# ESP32.net
KiCad netlist of a schematic drawn in Altium Designer
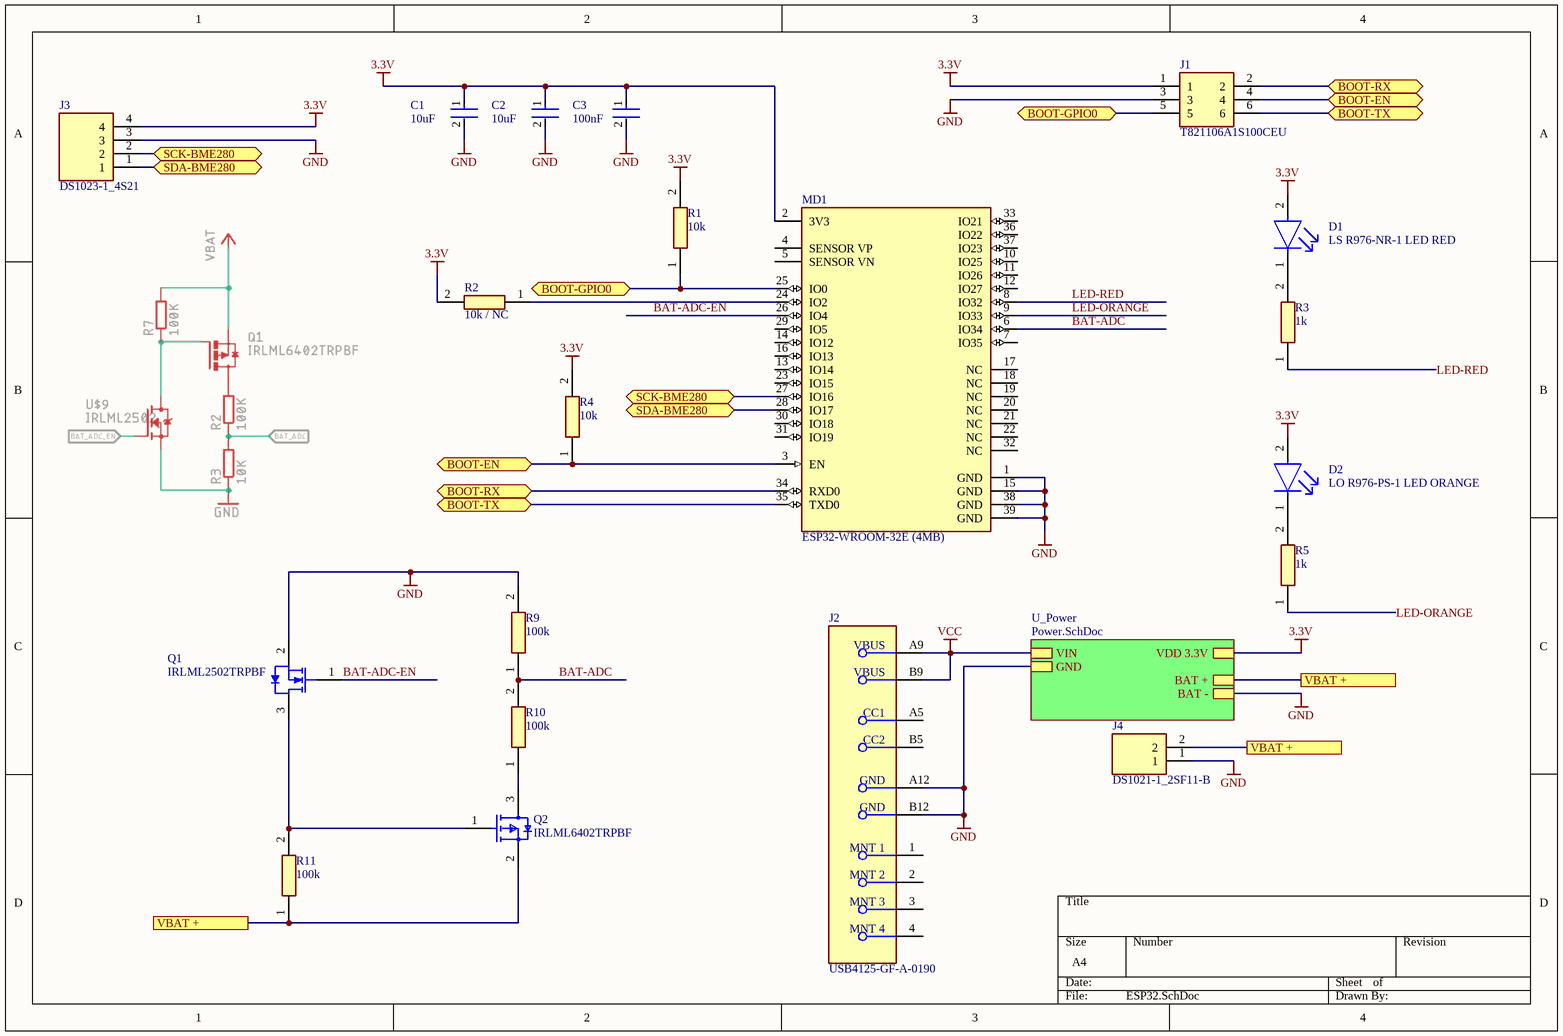
[diagram p0: ESP32.SchDoc]

(export (version "E")
  (design (tool "Eeschema 10.0.6"))
  (components
    (comp (ref "C1")
      (value "10uF")
      (footprint "FP-0805-L_2_01_0_2-W_1_25-IPC_B")
      (description "Automotive Ceramic Capacitor, 0805, 22nF, 5%, X7R, 15%, 100V")
      (fields (field (name "TOLERANCE") "5%"))
      (libsource (lib "Altium Content Vault") (part "b4654b650e69147ec39a6b967a45e02"))
    )
    (comp (ref "C2")
      (value "10uF")
      (footprint "FP-0805-L_2_01_0_2-W_1_25-IPC_B")
      (description "Automotive Ceramic Capacitor, 0805, 22nF, 5%, X7R, 15%, 100V")
      (fields (field (name "TOLERANCE") "5%"))
      (libsource (lib "Altium Content Vault") (part "b4654b650e69147ec39a6b967a45e02"))
    )
    (comp (ref "C3")
      (value "100nF")
      (footprint "FP-0805-L_2_01_0_2-W_1_25-IPC_B")
      (description "Automotive Ceramic Capacitor, 0805, 22nF, 5%, X7R, 15%, 100V")
      (fields (field (name "TOLERANCE") "5%"))
      (libsource (lib "Altium Content Vault") (part "b4654b650e69147ec39a6b967a45e02"))
    )
    (comp (ref "D1")
      (value "LS R976-NR-1 LED RED")
      (footprint "FP-LS_R976-MFG")
      (description "LED RED DIFFUSED 0805 SMD")
      (libsource (lib "Altium Content Vault") (part "8706943c75ba83719d021d2fdc84c58"))
    )
    (comp (ref "D2")
      (value "LO R976-PS-1 LED ORANGE")
      (footprint "FP-LO_R976-MFG")
      (description "LED ORANGE DIFFUSED 0805 SMD")
      (libsource (lib "Altium Content Vault") (part "8706943c75ba83719d021d2fdc84c58"))
    )
    (comp (ref "J1")
      (value "T821106A1S100CEU")
      (footprint "SamacSys:SHDR6W64P254X254_2X3_1524X895X915P")
      (description "Connector")
      (libsource (lib "*") (part "T821106A1S100CEU"))
    )
    (comp (ref "J2")
      (value "USB4125-GF-A-0190")
      (footprint "FP-USB4125-GF-A-0190-MFG")
      (description "CONN RCPT TYPE C 6P SMD RA")
      (libsource (lib "Altium Content Vault") (part "a055484d46e58b234844902c9fd883a"))
    )
    (comp (ref "J3")
      (value "DS1023-1_4S21")
      (footprint "SamacSys:RHDR4W60P0X254_1X4_1016X250X840P")
      (description "Connector")
      (fields (field (name "MANUFACTURER_PART_NUMBER") "DS1023-1*4S21"))
      (libsource (lib "*") (part "DS1023-1_4S21"))
    )
    (comp (ref "J4")
      (value "DS1021-1_2SF11-B")
      (footprint "SamacSys:HDRV2W64P0X254_1X2_508X254X588P")
      (description "Connector")
      (fields (field (name "MANUFACTURER_PART_NUMBER") "DS1021-1*2SF11-B"))
      (libsource (lib "SamacSys") (part "DS1021-1_2SF11-B"))
    )
    (comp (ref "MD1")
      (value "ESP32-WROOM-32E (4MB)")
      (footprint "FP-ESP32-WROOM-32E_4MB-MFG")
      (description "RX TXRX MOD WIFI TRACE ANT SMD")
      (libsource (lib "Altium Content Vault") (part "7f842c3463a9561e2f6f9fdcd687e0f"))
    )
    (comp (ref "Q1")
      (value "IRLML2502TRPBF")
      (footprint "INTR-SOT-23-3_V")
      (description "N-Channel HEXFET(R) Power MOSFET, 20 V VDS, +/- 12 V VGS, 4.2 A, 3-Pin SOT23, RoHS, Tape and Reel")
      (fields (field (name "MANUFACTURER") "International Rectifier"))
      (libsource (lib "Altium Content Vault") (part "NEMOS-GSD-3"))
    )
    (comp (ref "Q2")
      (value "IRLML6402TRPBF")
      (footprint "FP-Micro3-MFG")
      (description "MOSFET P-CH 20V 3.7A SOT-23")
      (fields
        (field (name "OCTOPART") "https://octopart.com/irlml6402trpbf-infineon-65874989")
        (field (name "MANUFACTURER") "Infineon")
      )
      (libsource (lib "Altium Content Vault") (part "566027c8dc92b5207d53ac25ab3eb60"))
    )
    (comp (ref "R1")
      (value "10k")
      (footprint "SamacSys:RESC2013X65N")
      (description "Resistor")
      (fields (field (name "MANUFACTURER_PART_NUMBER") "0805W8F1000T5E"))
      (libsource (lib "*") (part "0805W8F1000T5E"))
    )
    (comp (ref "R2")
      (value "10k / NC")
      (footprint "SamacSys:RESC2013X65N")
      (description "Resistor")
      (fields (field (name "MANUFACTURER_PART_NUMBER") "0805W8F1000T5E"))
      (libsource (lib "") (part "0805W8F1000T5E_1"))
    )
    (comp (ref "R3")
      (value "1k")
      (footprint "SamacSys:RESC2013X65N")
      (description "Resistor")
      (fields (field (name "MANUFACTURER_PART_NUMBER") "0805W8F1000T5E"))
      (libsource (lib "*") (part "0805W8F1000T5E"))
    )
    (comp (ref "R4")
      (value "10k")
      (footprint "SamacSys:RESC2013X65N")
      (description "Resistor")
      (fields (field (name "MANUFACTURER_PART_NUMBER") "0805W8F1000T5E"))
      (libsource (lib "*") (part "0805W8F1000T5E"))
    )
    (comp (ref "R5")
      (value "1k")
      (footprint "SamacSys:RESC2013X65N")
      (description "Resistor")
      (fields (field (name "MANUFACTURER_PART_NUMBER") "0805W8F1000T5E"))
      (libsource (lib "*") (part "0805W8F1000T5E"))
    )
    (comp (ref "R9")
      (value "100k")
      (footprint "SamacSys:RESC2013X65N")
      (description "Resistor")
      (fields (field (name "MANUFACTURER_PART_NUMBER") "0805W8F1000T5E"))
      (libsource (lib "*") (part "0805W8F1000T5E"))
    )
    (comp (ref "R10")
      (value "100k")
      (footprint "SamacSys:RESC2013X65N")
      (description "Resistor")
      (fields (field (name "MANUFACTURER_PART_NUMBER") "0805W8F1000T5E"))
      (libsource (lib "*") (part "0805W8F1000T5E"))
    )
    (comp (ref "R11")
      (value "100k")
      (footprint "SamacSys:RESC2013X65N")
      (description "Resistor")
      (fields (field (name "MANUFACTURER_PART_NUMBER") "0805W8F1000T5E"))
      (libsource (lib "*") (part "0805W8F1000T5E"))
    )
  )
  (nets
    (net (code "1") (name "/BAT-ADC") (class "Default")
      (node (ref "MD1") (pin "6") (pinfunction "IO34_6") (pintype "bidirectional"))
      (node (ref "R10") (pin "2") (pinfunction "2_2") (pintype "passive"))
      (node (ref "R9") (pin "1") (pinfunction "1_1") (pintype "passive"))
    )
    (net (code "2") (name "/BAT-ADC-EN") (class "Default")
      (node (ref "MD1") (pin "26") (pinfunction "IO4_26") (pintype "bidirectional"))
      (node (ref "Q1") (pin "1") (pinfunction "G_1") (pintype "passive"))
    )
    (net (code "3") (name "/BOOT-EN") (class "Default")
      (node (ref "J1") (pin "4") (pinfunction "4_4") (pintype "passive"))
      (node (ref "MD1") (pin "3") (pinfunction "EN_3") (pintype "input"))
      (node (ref "R4") (pin "1") (pinfunction "1_1") (pintype "passive"))
    )
    (net (code "4") (name "/BOOT-GPIO0") (class "Default")
      (node (ref "J1") (pin "5") (pinfunction "5_5") (pintype "passive"))
      (node (ref "MD1") (pin "25") (pinfunction "IO0_25") (pintype "bidirectional"))
      (node (ref "R1") (pin "1") (pinfunction "1_1") (pintype "passive"))
    )
    (net (code "5") (name "/BOOT-RX") (class "Default")
      (node (ref "J1") (pin "2") (pinfunction "2_2") (pintype "passive"))
      (node (ref "MD1") (pin "34") (pinfunction "RXD0_34") (pintype "bidirectional"))
    )
    (net (code "6") (name "/BOOT-TX") (class "Default")
      (node (ref "J1") (pin "6") (pinfunction "6_6") (pintype "passive"))
      (node (ref "MD1") (pin "35") (pinfunction "TXD0_35") (pintype "bidirectional"))
    )
    (net (code "7") (name "/LED-ORANGE") (class "Default")
      (node (ref "MD1") (pin "9") (pinfunction "IO33_9") (pintype "bidirectional"))
      (node (ref "R5") (pin "1") (pinfunction "1_1") (pintype "passive"))
    )
    (net (code "8") (name "/LED-RED") (class "Default")
      (node (ref "MD1") (pin "8") (pinfunction "IO32_8") (pintype "bidirectional"))
      (node (ref "R3") (pin "1") (pinfunction "1_1") (pintype "passive"))
    )
    (net (code "9") (name "/SCK-BME280") (class "Default")
      (node (ref "J3") (pin "2") (pinfunction "2_2") (pintype "passive"))
      (node (ref "MD1") (pin "27") (pinfunction "IO16_27") (pintype "bidirectional"))
    )
    (net (code "10") (name "/SDA-BME280") (class "Default")
      (node (ref "J3") (pin "1") (pinfunction "1_1") (pintype "passive"))
      (node (ref "MD1") (pin "28") (pinfunction "IO17_28") (pintype "bidirectional"))
    )
    (net (code "11") (name "/VBAT +") (class "Default")
      (node (ref "J4") (pin "2") (pinfunction "2_2") (pintype "passive"))
      (node (ref "Q2") (pin "2") (pinfunction "S_2") (pintype "passive"))
      (node (ref "R11") (pin "1") (pinfunction "1_1") (pintype "passive"))
    )
    (net (code "12") (name "3.3V") (class "Default")
      (node (ref "C1") (pin "1") (pinfunction "1_1") (pintype "passive"))
      (node (ref "C2") (pin "1") (pinfunction "1_1") (pintype "passive"))
      (node (ref "C3") (pin "1") (pinfunction "1_1") (pintype "passive"))
      (node (ref "D1") (pin "2") (pinfunction "A_2") (pintype "passive"))
      (node (ref "D2") (pin "2") (pinfunction "A_2") (pintype "passive"))
      (node (ref "J1") (pin "1") (pinfunction "1_1") (pintype "passive"))
      (node (ref "J3") (pin "4") (pinfunction "4_4") (pintype "passive"))
      (node (ref "MD1") (pin "2") (pinfunction "3V3_2") (pintype "passive"))
      (node (ref "R1") (pin "2") (pinfunction "2_2") (pintype "passive"))
      (node (ref "R2") (pin "2") (pinfunction "2_2") (pintype "passive"))
      (node (ref "R4") (pin "2") (pinfunction "2_2") (pintype "passive"))
    )
    (net (code "13") (name "GND") (class "Default")
      (node (ref "C1") (pin "2") (pinfunction "2_2") (pintype "passive"))
      (node (ref "C2") (pin "2") (pinfunction "2_2") (pintype "passive"))
      (node (ref "C3") (pin "2") (pinfunction "2_2") (pintype "passive"))
      (node (ref "J1") (pin "3") (pinfunction "3_3") (pintype "passive"))
      (node (ref "J2") (pin "A12") (pinfunction "GND_A12") (pintype "passive"))
      (node (ref "J2") (pin "B12") (pinfunction "GND_B12") (pintype "passive"))
      (node (ref "J3") (pin "3") (pinfunction "3_3") (pintype "passive"))
      (node (ref "J4") (pin "1") (pinfunction "1_1") (pintype "passive"))
      (node (ref "MD1") (pin "1") (pinfunction "GND_1") (pintype "passive"))
      (node (ref "MD1") (pin "15") (pinfunction "GND_15") (pintype "power_in"))
      (node (ref "MD1") (pin "38") (pinfunction "GND_38") (pintype "passive"))
      (node (ref "MD1") (pin "39") (pinfunction "GND_39") (pintype "passive"))
      (node (ref "Q1") (pin "2") (pinfunction "S_2") (pintype "passive"))
      (node (ref "R9") (pin "2") (pinfunction "2_2") (pintype "passive"))
    )
    (net (code "14") (name "Net-(D1-C)") (class "Default")
      (node (ref "D1") (pin "1") (pinfunction "C_1") (pintype "passive"))
      (node (ref "R3") (pin "2") (pinfunction "2_2") (pintype "passive"))
    )
    (net (code "15") (name "Net-(D2-C)") (class "Default")
      (node (ref "D2") (pin "1") (pinfunction "C_1") (pintype "passive"))
      (node (ref "R5") (pin "2") (pinfunction "2_2") (pintype "passive"))
    )
    (net (code "16") (name "Net-(MD1-IO2)") (class "Default")
      (node (ref "MD1") (pin "24") (pinfunction "IO2_24") (pintype "bidirectional"))
      (node (ref "R2") (pin "1") (pinfunction "1_1") (pintype "passive"))
    )
    (net (code "17") (name "Net-(Q1-D)") (class "Default")
      (node (ref "Q1") (pin "3") (pinfunction "D_3") (pintype "passive"))
      (node (ref "Q2") (pin "1") (pinfunction "G_1") (pintype "passive"))
      (node (ref "R11") (pin "2") (pinfunction "2_2") (pintype "passive"))
    )
    (net (code "18") (name "Net-(Q2-D)") (class "Default")
      (node (ref "Q2") (pin "3") (pinfunction "D_3") (pintype "passive"))
      (node (ref "R10") (pin "1") (pinfunction "1_1") (pintype "passive"))
    )
    (net (code "19") (name "VCC") (class "Default")
      (node (ref "J2") (pin "A9") (pinfunction "VBUS_A9") (pintype "passive"))
      (node (ref "J2") (pin "B9") (pinfunction "VBUS_B9") (pintype "passive"))
    )
    (net (code "20") (name "unconnected-(J2-CC1-PadA5)") (class "Default")
      (node (ref "J2") (pin "A5") (pinfunction "CC1_A5") (pintype "passive"))
    )
    (net (code "21") (name "unconnected-(J2-CC2-PadB5)") (class "Default")
      (node (ref "J2") (pin "B5") (pinfunction "CC2_B5") (pintype "passive"))
    )
    (net (code "22") (name "unconnected-(J2-MNT_1-Pad1)") (class "Default")
      (node (ref "J2") (pin "1") (pinfunction "MNT_1_1") (pintype "passive"))
    )
    (net (code "23") (name "unconnected-(J2-MNT_2-Pad2)") (class "Default")
      (node (ref "J2") (pin "2") (pinfunction "MNT_2_2") (pintype "passive"))
    )
    (net (code "24") (name "unconnected-(J2-MNT_3-Pad3)") (class "Default")
      (node (ref "J2") (pin "3") (pinfunction "MNT_3_3") (pintype "passive"))
    )
    (net (code "25") (name "unconnected-(J2-MNT_4-Pad4)") (class "Default")
      (node (ref "J2") (pin "4") (pinfunction "MNT_4_4") (pintype "passive"))
    )
    (net (code "26") (name "unconnected-(MD1-IO5-Pad29)") (class "Default")
      (node (ref "MD1") (pin "29") (pinfunction "IO5_29") (pintype "bidirectional"))
    )
    (net (code "27") (name "unconnected-(MD1-IO12-Pad14)") (class "Default")
      (node (ref "MD1") (pin "14") (pinfunction "IO12_14") (pintype "bidirectional"))
    )
    (net (code "28") (name "unconnected-(MD1-IO13-Pad16)") (class "Default")
      (node (ref "MD1") (pin "16") (pinfunction "IO13_16") (pintype "bidirectional"))
    )
    (net (code "29") (name "unconnected-(MD1-IO14-Pad13)") (class "Default")
      (node (ref "MD1") (pin "13") (pinfunction "IO14_13") (pintype "bidirectional"))
    )
    (net (code "30") (name "unconnected-(MD1-IO15-Pad23)") (class "Default")
      (node (ref "MD1") (pin "23") (pinfunction "IO15_23") (pintype "bidirectional"))
    )
    (net (code "31") (name "unconnected-(MD1-IO18-Pad30)") (class "Default")
      (node (ref "MD1") (pin "30") (pinfunction "IO18_30") (pintype "bidirectional"))
    )
    (net (code "32") (name "unconnected-(MD1-IO19-Pad31)") (class "Default")
      (node (ref "MD1") (pin "31") (pinfunction "IO19_31") (pintype "bidirectional"))
    )
    (net (code "33") (name "unconnected-(MD1-IO21-Pad33)") (class "Default")
      (node (ref "MD1") (pin "33") (pinfunction "IO21_33") (pintype "bidirectional"))
    )
    (net (code "34") (name "unconnected-(MD1-IO22-Pad36)") (class "Default")
      (node (ref "MD1") (pin "36") (pinfunction "IO22_36") (pintype "bidirectional"))
    )
    (net (code "35") (name "unconnected-(MD1-IO23-Pad37)") (class "Default")
      (node (ref "MD1") (pin "37") (pinfunction "IO23_37") (pintype "bidirectional"))
    )
    (net (code "36") (name "unconnected-(MD1-IO25-Pad10)") (class "Default")
      (node (ref "MD1") (pin "10") (pinfunction "IO25_10") (pintype "bidirectional"))
    )
    (net (code "37") (name "unconnected-(MD1-IO26-Pad11)") (class "Default")
      (node (ref "MD1") (pin "11") (pinfunction "IO26_11") (pintype "bidirectional"))
    )
    (net (code "38") (name "unconnected-(MD1-IO27-Pad12)") (class "Default")
      (node (ref "MD1") (pin "12") (pinfunction "IO27_12") (pintype "bidirectional"))
    )
    (net (code "39") (name "unconnected-(MD1-IO35-Pad7)") (class "Default")
      (node (ref "MD1") (pin "7") (pinfunction "IO35_7") (pintype "bidirectional"))
    )
    (net (code "40") (name "unconnected-(MD1-NC-Pad17)") (class "Default")
      (node (ref "MD1") (pin "17") (pinfunction "NC_17") (pintype "passive"))
    )
    (net (code "41") (name "unconnected-(MD1-NC-Pad18)") (class "Default")
      (node (ref "MD1") (pin "18") (pinfunction "NC_18") (pintype "passive"))
    )
    (net (code "42") (name "unconnected-(MD1-NC-Pad19)") (class "Default")
      (node (ref "MD1") (pin "19") (pinfunction "NC_19") (pintype "passive"))
    )
    (net (code "43") (name "unconnected-(MD1-NC-Pad20)") (class "Default")
      (node (ref "MD1") (pin "20") (pinfunction "NC_20") (pintype "passive"))
    )
    (net (code "44") (name "unconnected-(MD1-NC-Pad21)") (class "Default")
      (node (ref "MD1") (pin "21") (pinfunction "NC_21") (pintype "passive"))
    )
    (net (code "45") (name "unconnected-(MD1-NC-Pad22)") (class "Default")
      (node (ref "MD1") (pin "22") (pinfunction "NC_22") (pintype "passive"))
    )
    (net (code "46") (name "unconnected-(MD1-NC-Pad32)") (class "Default")
      (node (ref "MD1") (pin "32") (pinfunction "NC_32") (pintype "passive"))
    )
    (net (code "47") (name "unconnected-(MD1-SENSOR_VN-Pad5)") (class "Default")
      (node (ref "MD1") (pin "5") (pinfunction "SENSOR_VN_5") (pintype "passive"))
    )
    (net (code "48") (name "unconnected-(MD1-SENSOR_VP-Pad4)") (class "Default")
      (node (ref "MD1") (pin "4") (pinfunction "SENSOR_VP_4") (pintype "passive"))
    )
  )
)
